# servo-flipper.net
KiCad netlist of a schematic drawn in EasyEDA
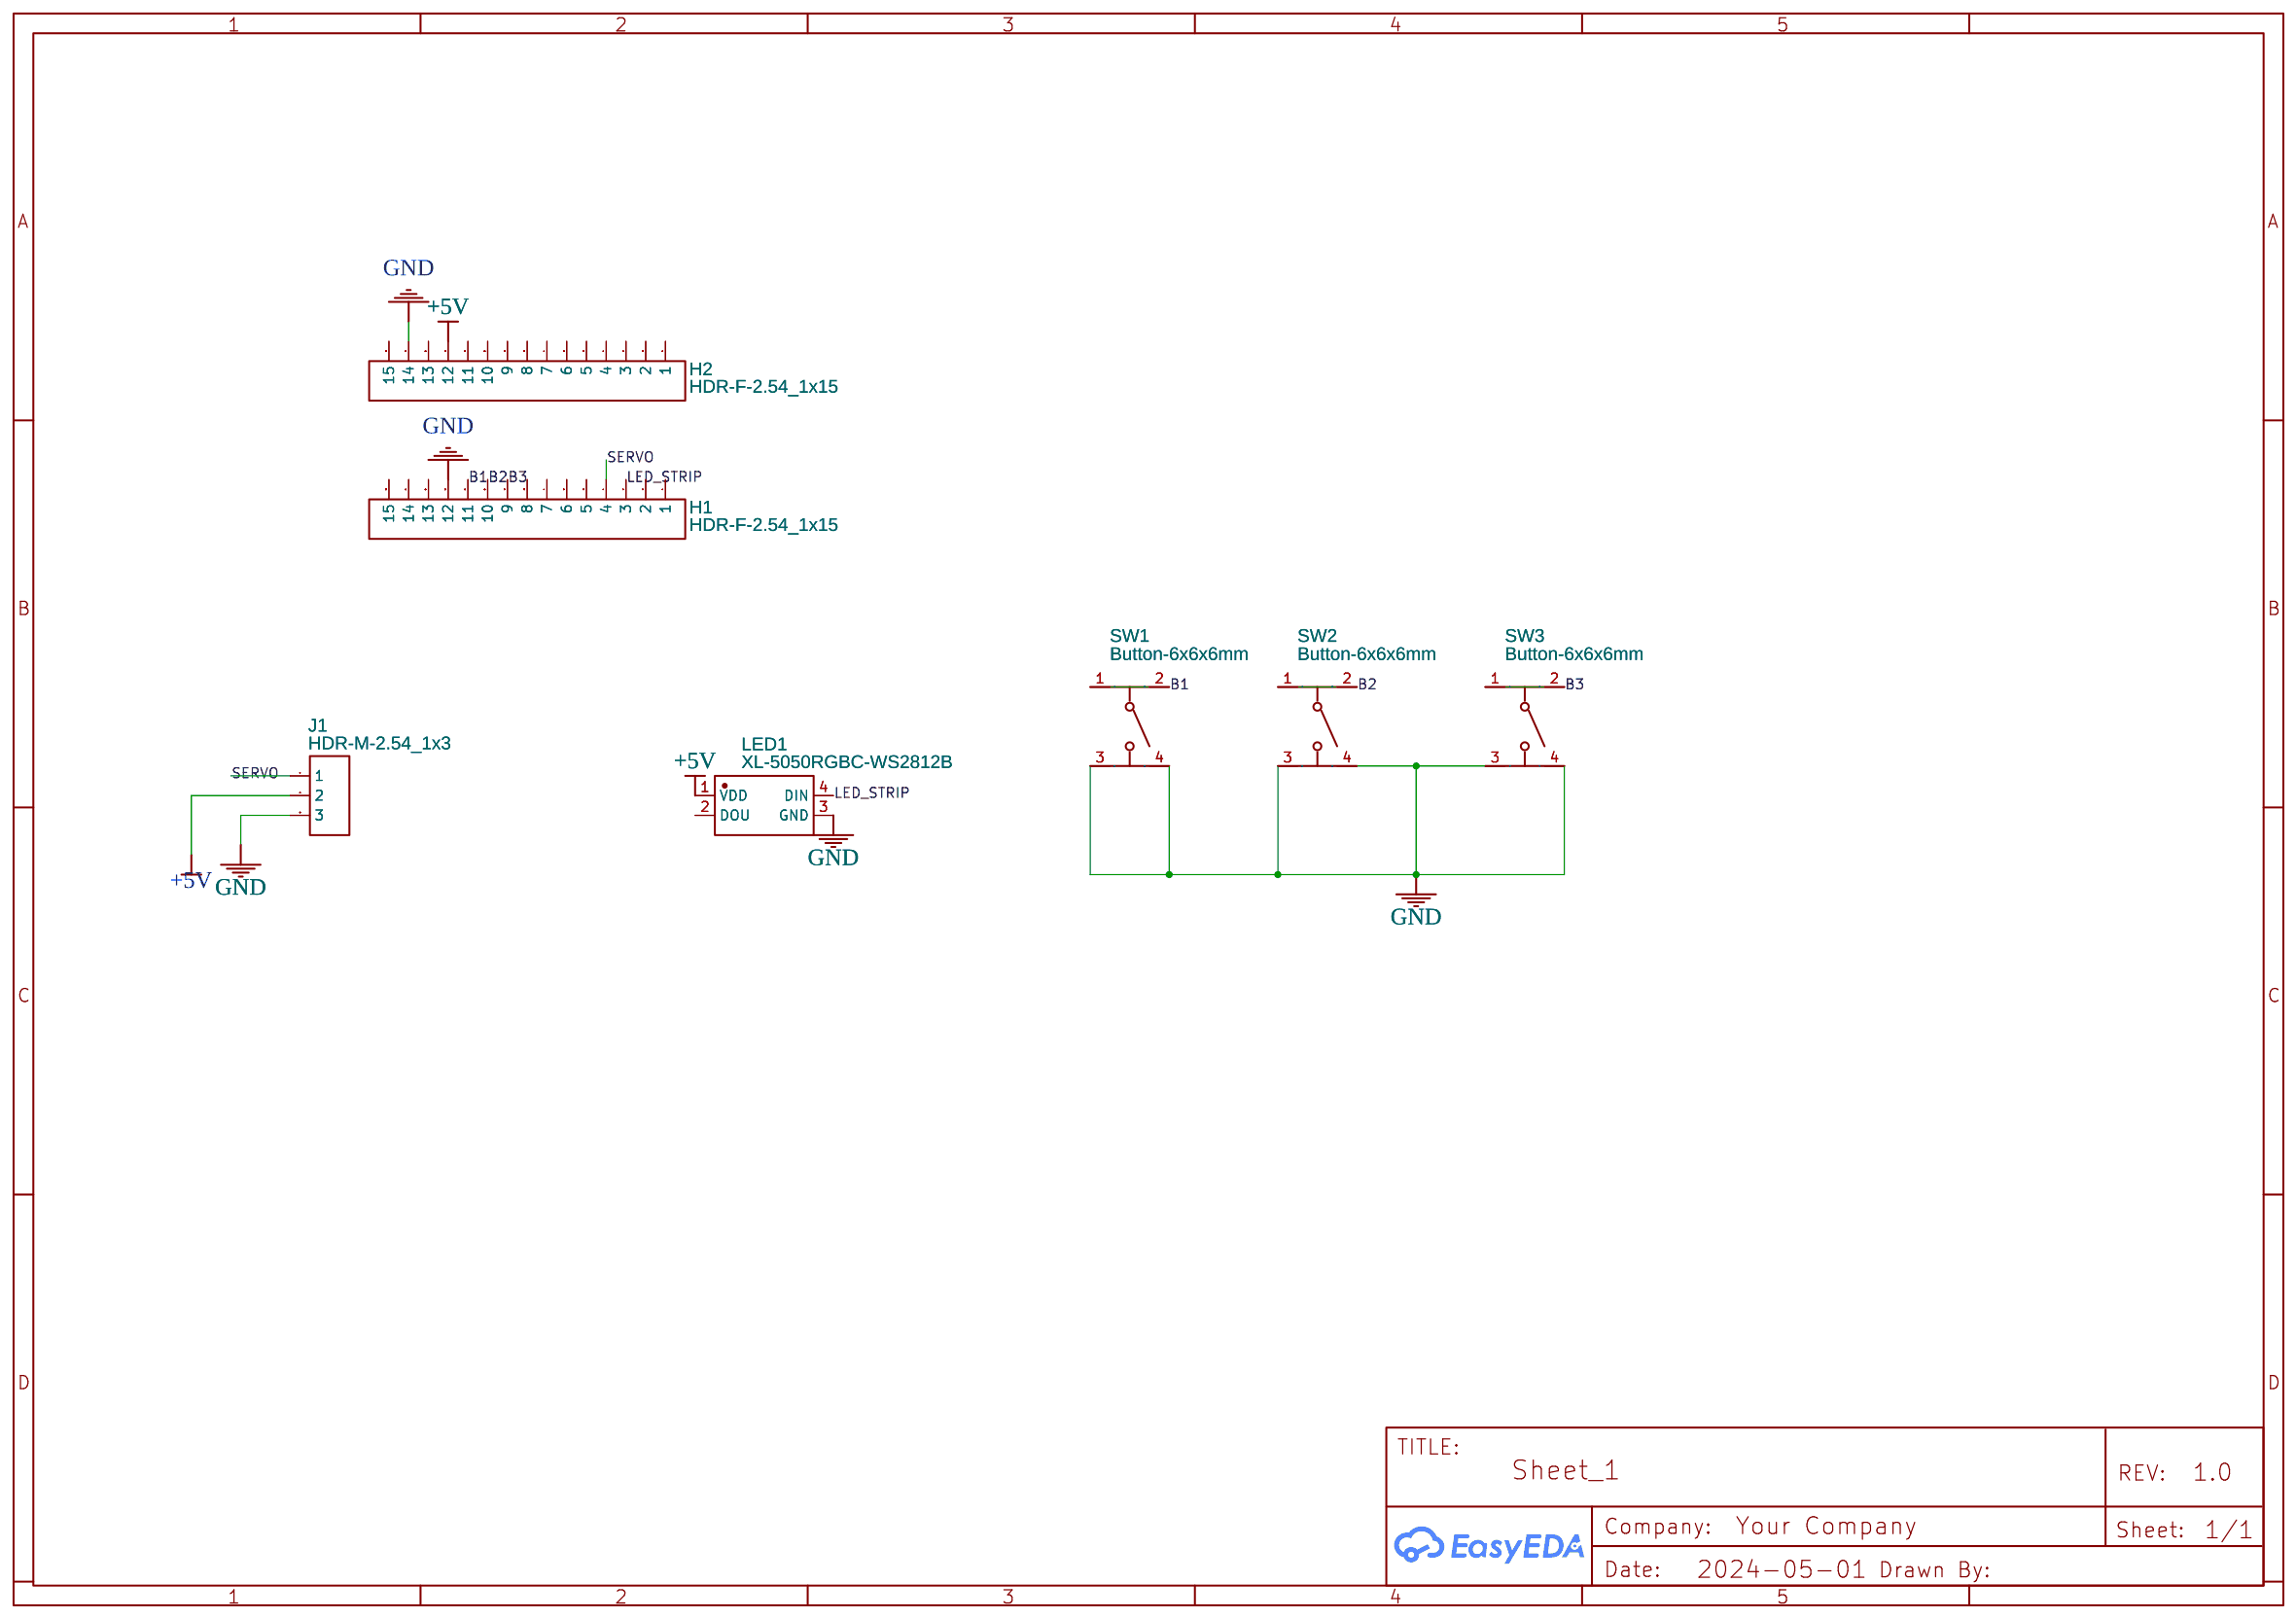
[diagram p0: schematic sheet]

(export (version "E")
  (design (tool "Eeschema 10.0.6"))
  (components
    (comp (ref "H1") (value "HDR-F-2.54_1x15") (libsource (lib "") (part "HDR-F-2.54_1x15")))
    (comp (ref "H2") (value "HDR-F-2.54_1x15") (libsource (lib "") (part "HDR-F-2.54_1x15")))
    (comp (ref "J1") (value "HDR-M-2.54_1x3") (libsource (lib "") (part "HDR-M-2.54_1x3")))
    (comp (ref "LED1")
      (value "XL-5050RGBC-WS2812B")
      (fields (field (name "Manufacturer") "XINGLIGHT(成兴光)"))
      (libsource (lib "") (part "XL-5050RGBC-WS2812B"))
    )
    (comp (ref "SW1")
      (value "Button-6x6x6mm")
      (fields
        (field (name "Manufacturer Part") "Switch,6*6*6Plastic head,260G, 0.25mm,Straight line")
        (field (name "Manufacturer") "BBJ")
      )
      (libsource (lib "") (part "Button-6x6x6mm"))
    )
    (comp (ref "SW2")
      (value "Button-6x6x6mm")
      (fields
        (field (name "Manufacturer Part") "Switch,6*6*6Plastic head,260G, 0.25mm,Straight line")
        (field (name "Manufacturer") "BBJ")
      )
      (libsource (lib "") (part "Button-6x6x6mm"))
    )
    (comp (ref "SW3")
      (value "Button-6x6x6mm")
      (fields
        (field (name "Manufacturer Part") "Switch,6*6*6Plastic head,260G, 0.25mm,Straight line")
        (field (name "Manufacturer") "BBJ")
      )
      (libsource (lib "") (part "Button-6x6x6mm"))
    )
  )
  (nets
    (net (code "1") (name "+5V") (class "Default")
      (node (ref "H2") (pin "12") (pinfunction "12_12") (pintype "unspecified"))
      (node (ref "J1") (pin "2") (pinfunction "2_2") (pintype "input"))
      (node (ref "LED1") (pin "1") (pinfunction "VDD_1") (pintype "unspecified"))
    )
    (net (code "2") (name "/B1") (class "Default")
      (node (ref "H1") (pin "11") (pinfunction "11_11") (pintype "unspecified"))
      (node (ref "SW1") (pin "1") (pinfunction "1_1") (pintype "unspecified"))
      (node (ref "SW1") (pin "2") (pinfunction "2_2") (pintype "unspecified"))
    )
    (net (code "3") (name "/B2") (class "Default")
      (node (ref "H1") (pin "10") (pinfunction "10_10") (pintype "unspecified"))
      (node (ref "SW2") (pin "1") (pinfunction "1_1") (pintype "unspecified"))
      (node (ref "SW2") (pin "2") (pinfunction "2_2") (pintype "unspecified"))
    )
    (net (code "4") (name "/B3") (class "Default")
      (node (ref "H1") (pin "9") (pinfunction "9_9") (pintype "unspecified"))
      (node (ref "SW3") (pin "1") (pinfunction "1_1") (pintype "unspecified"))
      (node (ref "SW3") (pin "2") (pinfunction "2_2") (pintype "unspecified"))
    )
    (net (code "5") (name "/LED_STRIP") (class "Default")
      (node (ref "H1") (pin "3") (pinfunction "3_3") (pintype "unspecified"))
      (node (ref "LED1") (pin "4") (pinfunction "DIN_4") (pintype "unspecified"))
    )
    (net (code "6") (name "/SERVO") (class "Default")
      (node (ref "H1") (pin "4") (pinfunction "4_4") (pintype "unspecified"))
      (node (ref "J1") (pin "1") (pinfunction "1_1") (pintype "input"))
    )
    (net (code "7") (name "GND") (class "Default")
      (node (ref "H1") (pin "12") (pinfunction "12_12") (pintype "unspecified"))
      (node (ref "H2") (pin "14") (pinfunction "14_14") (pintype "unspecified"))
      (node (ref "J1") (pin "3") (pinfunction "3_3") (pintype "input"))
      (node (ref "LED1") (pin "3") (pinfunction "GND_3") (pintype "unspecified"))
      (node (ref "SW1") (pin "3") (pinfunction "3_3") (pintype "unspecified"))
      (node (ref "SW1") (pin "4") (pinfunction "4_4") (pintype "unspecified"))
      (node (ref "SW2") (pin "3") (pinfunction "3_3") (pintype "unspecified"))
      (node (ref "SW2") (pin "4") (pinfunction "4_4") (pintype "unspecified"))
      (node (ref "SW3") (pin "3") (pinfunction "3_3") (pintype "unspecified"))
      (node (ref "SW3") (pin "4") (pinfunction "4_4") (pintype "unspecified"))
    )
    (net (code "8") (name "unconnected-(H1-Pad1)") (class "Default")
      (node (ref "H1") (pin "1") (pinfunction "1_1") (pintype "unspecified"))
    )
    (net (code "9") (name "unconnected-(H1-Pad2)") (class "Default")
      (node (ref "H1") (pin "2") (pinfunction "2_2") (pintype "unspecified"))
    )
    (net (code "10") (name "unconnected-(H1-Pad5)") (class "Default")
      (node (ref "H1") (pin "5") (pinfunction "5_5") (pintype "unspecified"))
    )
    (net (code "11") (name "unconnected-(H1-Pad6)") (class "Default")
      (node (ref "H1") (pin "6") (pinfunction "6_6") (pintype "unspecified"))
    )
    (net (code "12") (name "unconnected-(H1-Pad7)") (class "Default")
      (node (ref "H1") (pin "7") (pinfunction "7_7") (pintype "unspecified"))
    )
    (net (code "13") (name "unconnected-(H1-Pad8)") (class "Default")
      (node (ref "H1") (pin "8") (pinfunction "8_8") (pintype "unspecified"))
    )
    (net (code "14") (name "unconnected-(H1-Pad13)") (class "Default")
      (node (ref "H1") (pin "13") (pinfunction "13_13") (pintype "unspecified"))
    )
    (net (code "15") (name "unconnected-(H1-Pad14)") (class "Default")
      (node (ref "H1") (pin "14") (pinfunction "14_14") (pintype "unspecified"))
    )
    (net (code "16") (name "unconnected-(H1-Pad15)") (class "Default")
      (node (ref "H1") (pin "15") (pinfunction "15_15") (pintype "unspecified"))
    )
    (net (code "17") (name "unconnected-(H2-Pad1)") (class "Default")
      (node (ref "H2") (pin "1") (pinfunction "1_1") (pintype "unspecified"))
    )
    (net (code "18") (name "unconnected-(H2-Pad2)") (class "Default")
      (node (ref "H2") (pin "2") (pinfunction "2_2") (pintype "unspecified"))
    )
    (net (code "19") (name "unconnected-(H2-Pad3)") (class "Default")
      (node (ref "H2") (pin "3") (pinfunction "3_3") (pintype "unspecified"))
    )
    (net (code "20") (name "unconnected-(H2-Pad4)") (class "Default")
      (node (ref "H2") (pin "4") (pinfunction "4_4") (pintype "unspecified"))
    )
    (net (code "21") (name "unconnected-(H2-Pad5)") (class "Default")
      (node (ref "H2") (pin "5") (pinfunction "5_5") (pintype "unspecified"))
    )
    (net (code "22") (name "unconnected-(H2-Pad6)") (class "Default")
      (node (ref "H2") (pin "6") (pinfunction "6_6") (pintype "unspecified"))
    )
    (net (code "23") (name "unconnected-(H2-Pad7)") (class "Default")
      (node (ref "H2") (pin "7") (pinfunction "7_7") (pintype "unspecified"))
    )
    (net (code "24") (name "unconnected-(H2-Pad8)") (class "Default")
      (node (ref "H2") (pin "8") (pinfunction "8_8") (pintype "unspecified"))
    )
    (net (code "25") (name "unconnected-(H2-Pad9)") (class "Default")
      (node (ref "H2") (pin "9") (pinfunction "9_9") (pintype "unspecified"))
    )
    (net (code "26") (name "unconnected-(H2-Pad10)") (class "Default")
      (node (ref "H2") (pin "10") (pinfunction "10_10") (pintype "unspecified"))
    )
    (net (code "27") (name "unconnected-(H2-Pad11)") (class "Default")
      (node (ref "H2") (pin "11") (pinfunction "11_11") (pintype "unspecified"))
    )
    (net (code "28") (name "unconnected-(H2-Pad13)") (class "Default")
      (node (ref "H2") (pin "13") (pinfunction "13_13") (pintype "unspecified"))
    )
    (net (code "29") (name "unconnected-(H2-Pad15)") (class "Default")
      (node (ref "H2") (pin "15") (pinfunction "15_15") (pintype "unspecified"))
    )
    (net (code "30") (name "unconnected-(LED1-DOU-Pad2)") (class "Default")
      (node (ref "LED1") (pin "2") (pinfunction "DOU_2") (pintype "unspecified"))
    )
  )
)
